# TEH.net
KiCad netlist of a schematic drawn in EAGLE
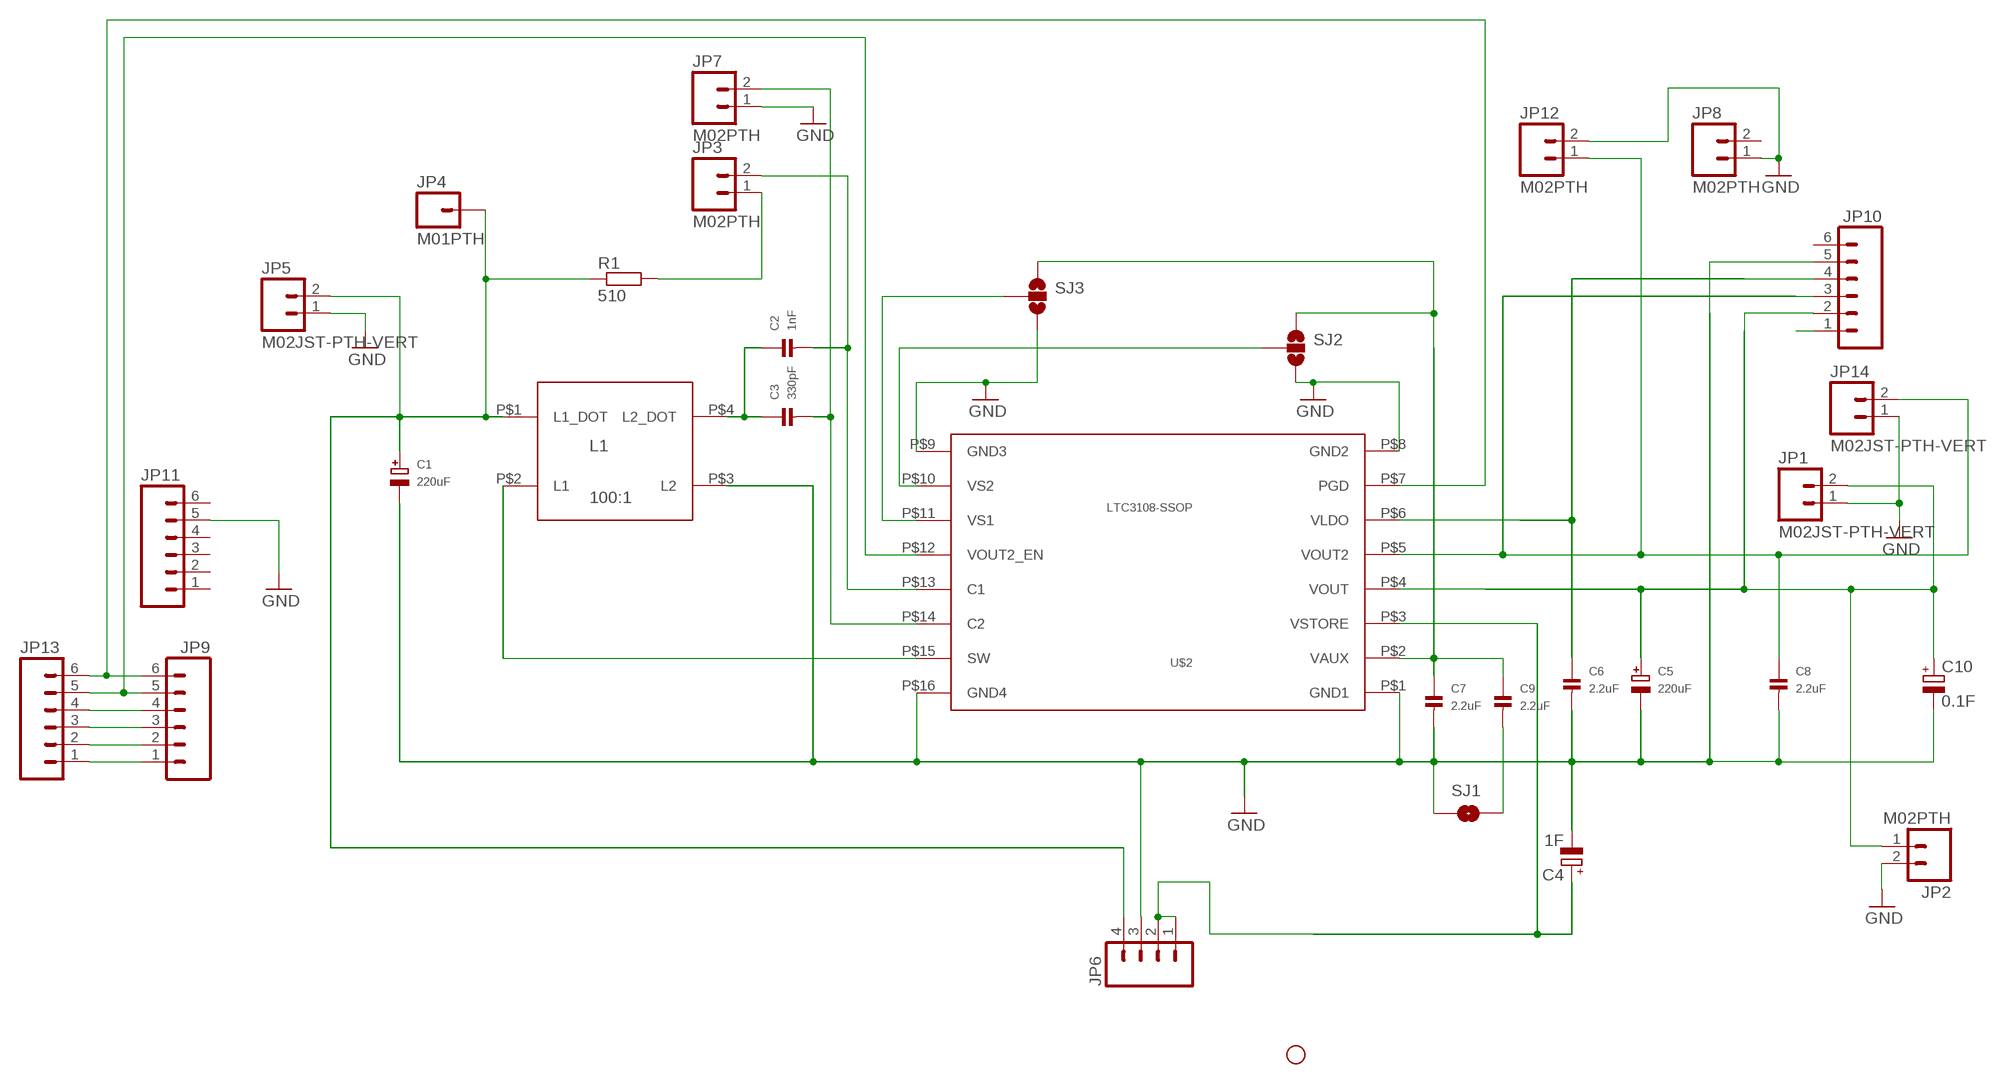
[diagram p0: schematic, sheet 1]

(export (version "E")
  (design (tool "Eeschema 10.0.6"))
  (components
    (comp (ref "C1")
      (value "220uF")
      (footprint "eagle-import:EIA7343-31_D-R")
      (libsource (lib "eagle-import") (part "CAP_TANTALUMD/7343_REFLOW"))
    )
    (comp (ref "C2")
      (value "1nF")
      (footprint "eagle-import:0805")
      (libsource (lib "eagle-import") (part "CAP_CERAMIC0805"))
    )
    (comp (ref "C3")
      (value "330pF")
      (footprint "eagle-import:0805")
      (libsource (lib "eagle-import") (part "CAP_CERAMIC0805"))
    )
    (comp (ref "C4")
      (value "1F")
      (footprint "eagle-import:E5-13")
      (libsource (lib "eagle-import") (part "CPOL-EUE5-13"))
    )
    (comp (ref "C5")
      (value "220uF")
      (footprint "eagle-import:EIA7343-31_D-R")
      (libsource (lib "eagle-import") (part "CAP_TANTALUMD/7343_REFLOW"))
    )
    (comp (ref "C6")
      (value "2.2uF")
      (footprint "eagle-import:0805")
      (libsource (lib "eagle-import") (part "CAP_CERAMIC0805"))
    )
    (comp (ref "C7")
      (value "2.2uF")
      (footprint "eagle-import:0805")
      (libsource (lib "eagle-import") (part "CAP_CERAMIC0805"))
    )
    (comp (ref "C8")
      (value "2.2uF")
      (footprint "eagle-import:0805")
      (libsource (lib "eagle-import") (part "CAP_CERAMIC0805"))
    )
    (comp (ref "C9")
      (value "2.2uF")
      (footprint "eagle-import:0805")
      (libsource (lib "eagle-import") (part "CAP_CERAMIC0805"))
    )
    (comp (ref "C10")
      (value "0.1F")
      (footprint "eagle-import:E5-13")
      (libsource (lib "eagle-import") (part "CPOL-EUE5-13"))
    )
    (comp (ref "JP1")
      (value "M02JST-PTH-VERT")
      (footprint "eagle-import:JST-2-PTH-VERT")
      (libsource (lib "eagle-import") (part "M02JST-PTH-VERT"))
    )
    (comp (ref "JP2")
      (value "M02PTH")
      (footprint "eagle-import:1X02")
      (libsource (lib "eagle-import") (part "M02PTH"))
    )
    (comp (ref "JP3")
      (value "M02PTH")
      (footprint "eagle-import:1X02")
      (libsource (lib "eagle-import") (part "M02PTH"))
    )
    (comp (ref "JP4")
      (value "M01PTH")
      (footprint "eagle-import:1X01")
      (libsource (lib "eagle-import") (part "M01PTH"))
    )
    (comp (ref "JP5")
      (value "M02JST-PTH-VERT")
      (footprint "eagle-import:JST-2-PTH-VERT")
      (libsource (lib "eagle-import") (part "M02JST-PTH-VERT"))
    )
    (comp (ref "JP6")
      (value "M04PTH")
      (footprint "eagle-import:1X04")
      (libsource (lib "eagle-import") (part "M04PTH"))
    )
    (comp (ref "JP7")
      (value "M02PTH")
      (footprint "eagle-import:1X02")
      (libsource (lib "eagle-import") (part "M02PTH"))
    )
    (comp (ref "JP8")
      (value "M02PTH")
      (footprint "eagle-import:1X02")
      (libsource (lib "eagle-import") (part "M02PTH"))
    )
    (comp (ref "JP9")
      (value "M06NO_SILK")
      (footprint "eagle-import:1X06_NO_SILK")
      (libsource (lib "eagle-import") (part "M06NO_SILK"))
    )
    (comp (ref "JP10")
      (value "M06NO_SILK")
      (footprint "eagle-import:1X06_NO_SILK")
      (libsource (lib "eagle-import") (part "M06NO_SILK"))
    )
    (comp (ref "JP11")
      (value "M06NO_SILK")
      (footprint "eagle-import:1X06_NO_SILK")
      (libsource (lib "eagle-import") (part "M06NO_SILK"))
    )
    (comp (ref "JP12")
      (value "M02PTH")
      (footprint "eagle-import:1X02")
      (libsource (lib "eagle-import") (part "M02PTH"))
    )
    (comp (ref "JP13")
      (value "M06NO_SILK")
      (footprint "eagle-import:1X06_NO_SILK")
      (libsource (lib "eagle-import") (part "M06NO_SILK"))
    )
    (comp (ref "JP14")
      (value "M02JST-PTH-VERT")
      (footprint "eagle-import:JST-2-PTH-VERT")
      (libsource (lib "eagle-import") (part "M02JST-PTH-VERT"))
    )
    (comp (ref "L1")
      (value "100:1")
      (footprint "eagle-import:COILCRAFT_LPR6235")
      (libsource (lib "eagle-import") (part "COILCRAFT_LPR6235-752SML"))
    )
    (comp (ref "R1")
      (value "510")
      (footprint "eagle-import:R0805")
      (libsource (lib "eagle-import") (part "R-EU_R0805"))
    )
    (comp (ref "SJ1")
      (value "JUMPER-PAD-2-NOYES_SILK")
      (footprint "eagle-import:PAD-JUMPER-2-NO_YES_SILK")
      (libsource (lib "eagle-import") (part "JUMPER-PAD-2-NOYES_SILK"))
    )
    (comp (ref "SJ2")
      (value "SOLDERJUMPER_2WAYT")
      (footprint "eagle-import:SJ_2")
      (libsource (lib "eagle-import") (part "SOLDERJUMPER_2WAYT"))
    )
    (comp (ref "SJ3")
      (value "SOLDERJUMPER_2WAYT")
      (footprint "eagle-import:SJ_2")
      (libsource (lib "eagle-import") (part "SOLDERJUMPER_2WAYT"))
    )
    (comp (ref "STANDOFF2")
      (value "STAND-OFFTIGHT")
      (footprint "eagle-import:STAND-OFF-TIGHT")
      (libsource (lib "eagle-import") (part "STAND-OFFTIGHT"))
    )
    (comp (ref "U$2")
      (value "LTC3108-SSOP")
      (footprint "eagle-import:SSOP-GN-16")
      (libsource (lib "eagle-import") (part "LTC3108-SSOP"))
    )
  )
  (nets
    (net (code "1") (name "GND") (class "Default")
      (node (ref "C1") (pin "-") (pinfunction "-_-") (pintype "passive"))
      (node (ref "C10") (pin "-") (pinfunction "-_-") (pintype "passive"))
      (node (ref "C4") (pin "-") (pinfunction "-_-") (pintype "passive"))
      (node (ref "C5") (pin "-") (pinfunction "-_-") (pintype "passive"))
      (node (ref "C6") (pin "2") (pinfunction "P$2_2") (pintype "passive"))
      (node (ref "C7") (pin "2") (pinfunction "P$2_2") (pintype "passive"))
      (node (ref "C8") (pin "2") (pinfunction "P$2_2") (pintype "passive"))
      (node (ref "JP1") (pin "1") (pinfunction "1_1") (pintype "passive"))
      (node (ref "JP10") (pin "5") (pinfunction "5_5") (pintype "passive"))
      (node (ref "JP11") (pin "5") (pinfunction "5_5") (pintype "passive"))
      (node (ref "JP12") (pin "2") (pinfunction "2_2") (pintype "passive"))
      (node (ref "JP14") (pin "1") (pinfunction "1_1") (pintype "passive"))
      (node (ref "JP2") (pin "2") (pinfunction "2_2") (pintype "passive"))
      (node (ref "JP5") (pin "1") (pinfunction "1_1") (pintype "passive"))
      (node (ref "JP6") (pin "3") (pinfunction "3_3") (pintype "passive"))
      (node (ref "JP7") (pin "1") (pinfunction "1_1") (pintype "passive"))
      (node (ref "JP8") (pin "1") (pinfunction "1_1") (pintype "passive"))
      (node (ref "L1") (pin "P$3") (pinfunction "L2_P$3") (pintype "bidirectional"))
      (node (ref "SJ1") (pin "1") (pinfunction "1_1") (pintype "passive"))
      (node (ref "SJ2") (pin "3") (pinfunction "3_3") (pintype "passive"))
      (node (ref "SJ3") (pin "3") (pinfunction "3_3") (pintype "passive"))
      (node (ref "U$2") (pin "P$1") (pinfunction "GND1_P$1") (pintype "bidirectional"))
      (node (ref "U$2") (pin "P$16") (pinfunction "GND4_P$16") (pintype "bidirectional"))
      (node (ref "U$2") (pin "P$8") (pinfunction "GND2_P$8") (pintype "bidirectional"))
      (node (ref "U$2") (pin "P$9") (pinfunction "GND3_P$9") (pintype "bidirectional"))
    )
    (net (code "2") (name "Net-(C2-P$1)") (class "Default")
      (node (ref "C2") (pin "1") (pinfunction "P$1_1") (pintype "passive"))
      (node (ref "C3") (pin "1") (pinfunction "P$1_1") (pintype "passive"))
      (node (ref "L1") (pin "P$4") (pinfunction "L2_DOT_P$4") (pintype "bidirectional"))
    )
    (net (code "3") (name "Net-(C2-P$2)") (class "Default")
      (node (ref "C2") (pin "2") (pinfunction "P$2_2") (pintype "passive"))
      (node (ref "JP3") (pin "2") (pinfunction "2_2") (pintype "passive"))
      (node (ref "U$2") (pin "P$13") (pinfunction "C1_P$13") (pintype "bidirectional"))
    )
    (net (code "4") (name "Net-(C3-P$2)") (class "Default")
      (node (ref "C3") (pin "2") (pinfunction "P$2_2") (pintype "passive"))
      (node (ref "JP7") (pin "2") (pinfunction "2_2") (pintype "passive"))
      (node (ref "U$2") (pin "P$14") (pinfunction "C2_P$14") (pintype "bidirectional"))
    )
    (net (code "5") (name "Net-(C6-P$1)") (class "Default")
      (node (ref "C6") (pin "1") (pinfunction "P$1_1") (pintype "passive"))
      (node (ref "JP10") (pin "4") (pinfunction "4_4") (pintype "passive"))
      (node (ref "U$2") (pin "P$6") (pinfunction "VLDO_P$6") (pintype "bidirectional"))
    )
    (net (code "6") (name "Net-(C7-P$1)") (class "Default")
      (node (ref "C7") (pin "1") (pinfunction "P$1_1") (pintype "passive"))
      (node (ref "C9") (pin "1") (pinfunction "P$1_1") (pintype "passive"))
      (node (ref "SJ2") (pin "1") (pinfunction "1_1") (pintype "passive"))
      (node (ref "SJ3") (pin "1") (pinfunction "1_1") (pintype "passive"))
      (node (ref "U$2") (pin "P$2") (pinfunction "VAUX_P$2") (pintype "bidirectional"))
    )
    (net (code "7") (name "Net-(C8-P$1)") (class "Default")
      (node (ref "C8") (pin "1") (pinfunction "P$1_1") (pintype "passive"))
      (node (ref "JP10") (pin "3") (pinfunction "3_3") (pintype "passive"))
      (node (ref "JP12") (pin "1") (pinfunction "1_1") (pintype "passive"))
      (node (ref "JP14") (pin "2") (pinfunction "2_2") (pintype "passive"))
      (node (ref "U$2") (pin "P$5") (pinfunction "VOUT2_P$5") (pintype "bidirectional"))
    )
    (net (code "8") (name "Net-(C9-P$2)") (class "Default")
      (node (ref "C9") (pin "2") (pinfunction "P$2_2") (pintype "passive"))
      (node (ref "SJ1") (pin "2") (pinfunction "2_2") (pintype "passive"))
    )
    (net (code "9") (name "Net-(JP3-Pad1)") (class "Default")
      (node (ref "JP3") (pin "1") (pinfunction "1_1") (pintype "passive"))
      (node (ref "R1") (pin "2") (pinfunction "2_2") (pintype "passive"))
    )
    (net (code "10") (name "Net-(JP13-Pad1)") (class "Default")
      (node (ref "JP13") (pin "1") (pinfunction "1_1") (pintype "passive"))
      (node (ref "JP9") (pin "1") (pinfunction "1_1") (pintype "passive"))
    )
    (net (code "11") (name "Net-(JP13-Pad2)") (class "Default")
      (node (ref "JP13") (pin "2") (pinfunction "2_2") (pintype "passive"))
      (node (ref "JP9") (pin "2") (pinfunction "2_2") (pintype "passive"))
    )
    (net (code "12") (name "Net-(JP13-Pad3)") (class "Default")
      (node (ref "JP13") (pin "3") (pinfunction "3_3") (pintype "passive"))
      (node (ref "JP9") (pin "3") (pinfunction "3_3") (pintype "passive"))
    )
    (net (code "13") (name "Net-(JP13-Pad4)") (class "Default")
      (node (ref "JP13") (pin "4") (pinfunction "4_4") (pintype "passive"))
      (node (ref "JP9") (pin "4") (pinfunction "4_4") (pintype "passive"))
    )
    (net (code "14") (name "Net-(L1-L1)") (class "Default")
      (node (ref "L1") (pin "P$2") (pinfunction "L1_P$2") (pintype "bidirectional"))
      (node (ref "U$2") (pin "P$15") (pinfunction "SW_P$15") (pintype "bidirectional"))
    )
    (net (code "15") (name "Net-(L1-L1_DOT)") (class "Default")
      (node (ref "C1") (pin "+") (pinfunction "+_+") (pintype "passive"))
      (node (ref "JP4") (pin "1") (pinfunction "1_1") (pintype "passive"))
      (node (ref "JP5") (pin "2") (pinfunction "2_2") (pintype "passive"))
      (node (ref "JP6") (pin "4") (pinfunction "4_4") (pintype "passive"))
      (node (ref "L1") (pin "P$1") (pinfunction "L1_DOT_P$1") (pintype "bidirectional"))
      (node (ref "R1") (pin "1") (pinfunction "1_1") (pintype "passive"))
    )
    (net (code "16") (name "Net-(U$2-PGD)") (class "Default")
      (node (ref "JP13") (pin "6") (pinfunction "6_6") (pintype "passive"))
      (node (ref "JP9") (pin "6") (pinfunction "6_6") (pintype "passive"))
      (node (ref "U$2") (pin "P$7") (pinfunction "PGD_P$7") (pintype "bidirectional"))
    )
    (net (code "17") (name "Net-(U$2-VOUT)") (class "Default")
      (node (ref "C10") (pin "+") (pinfunction "+_+") (pintype "passive"))
      (node (ref "C5") (pin "+") (pinfunction "+_+") (pintype "passive"))
      (node (ref "JP1") (pin "2") (pinfunction "2_2") (pintype "passive"))
      (node (ref "JP10") (pin "2") (pinfunction "2_2") (pintype "passive"))
      (node (ref "JP2") (pin "1") (pinfunction "1_1") (pintype "passive"))
      (node (ref "U$2") (pin "P$4") (pinfunction "VOUT_P$4") (pintype "bidirectional"))
    )
    (net (code "18") (name "Net-(U$2-VOUT2_EN)") (class "Default")
      (node (ref "JP13") (pin "5") (pinfunction "5_5") (pintype "passive"))
      (node (ref "JP9") (pin "5") (pinfunction "5_5") (pintype "passive"))
      (node (ref "U$2") (pin "P$12") (pinfunction "VOUT2_EN_P$12") (pintype "bidirectional"))
    )
    (net (code "19") (name "Net-(U$2-VS1)") (class "Default")
      (node (ref "SJ3") (pin "2") (pinfunction "2_2") (pintype "passive"))
      (node (ref "U$2") (pin "P$11") (pinfunction "VS1_P$11") (pintype "bidirectional"))
    )
    (net (code "20") (name "Net-(U$2-VS2)") (class "Default")
      (node (ref "SJ2") (pin "2") (pinfunction "2_2") (pintype "passive"))
      (node (ref "U$2") (pin "P$10") (pinfunction "VS2_P$10") (pintype "bidirectional"))
    )
    (net (code "21") (name "Net-(U$2-VSTORE)") (class "Default")
      (node (ref "C4") (pin "+") (pinfunction "+_+") (pintype "passive"))
      (node (ref "JP6") (pin "1") (pinfunction "1_1") (pintype "passive"))
      (node (ref "JP6") (pin "2") (pinfunction "2_2") (pintype "passive"))
      (node (ref "U$2") (pin "P$3") (pinfunction "VSTORE_P$3") (pintype "bidirectional"))
    )
    (net (code "22") (name "unconnected-(JP8-Pad2)") (class "Default")
      (node (ref "JP8") (pin "2") (pinfunction "2_2") (pintype "passive"))
    )
    (net (code "23") (name "unconnected-(JP10-Pad1)") (class "Default")
      (node (ref "JP10") (pin "1") (pinfunction "1_1") (pintype "passive"))
    )
    (net (code "24") (name "unconnected-(JP10-Pad6)") (class "Default")
      (node (ref "JP10") (pin "6") (pinfunction "6_6") (pintype "passive"))
    )
    (net (code "25") (name "unconnected-(JP11-Pad1)") (class "Default")
      (node (ref "JP11") (pin "1") (pinfunction "1_1") (pintype "passive"))
    )
    (net (code "26") (name "unconnected-(JP11-Pad2)") (class "Default")
      (node (ref "JP11") (pin "2") (pinfunction "2_2") (pintype "passive"))
    )
    (net (code "27") (name "unconnected-(JP11-Pad3)") (class "Default")
      (node (ref "JP11") (pin "3") (pinfunction "3_3") (pintype "passive"))
    )
    (net (code "28") (name "unconnected-(JP11-Pad4)") (class "Default")
      (node (ref "JP11") (pin "4") (pinfunction "4_4") (pintype "passive"))
    )
    (net (code "29") (name "unconnected-(JP11-Pad6)") (class "Default")
      (node (ref "JP11") (pin "6") (pinfunction "6_6") (pintype "passive"))
    )
  )
)
